# EZ_FPGA_Bridge.net
KiCad netlist of a schematic drawn in Altium Designer
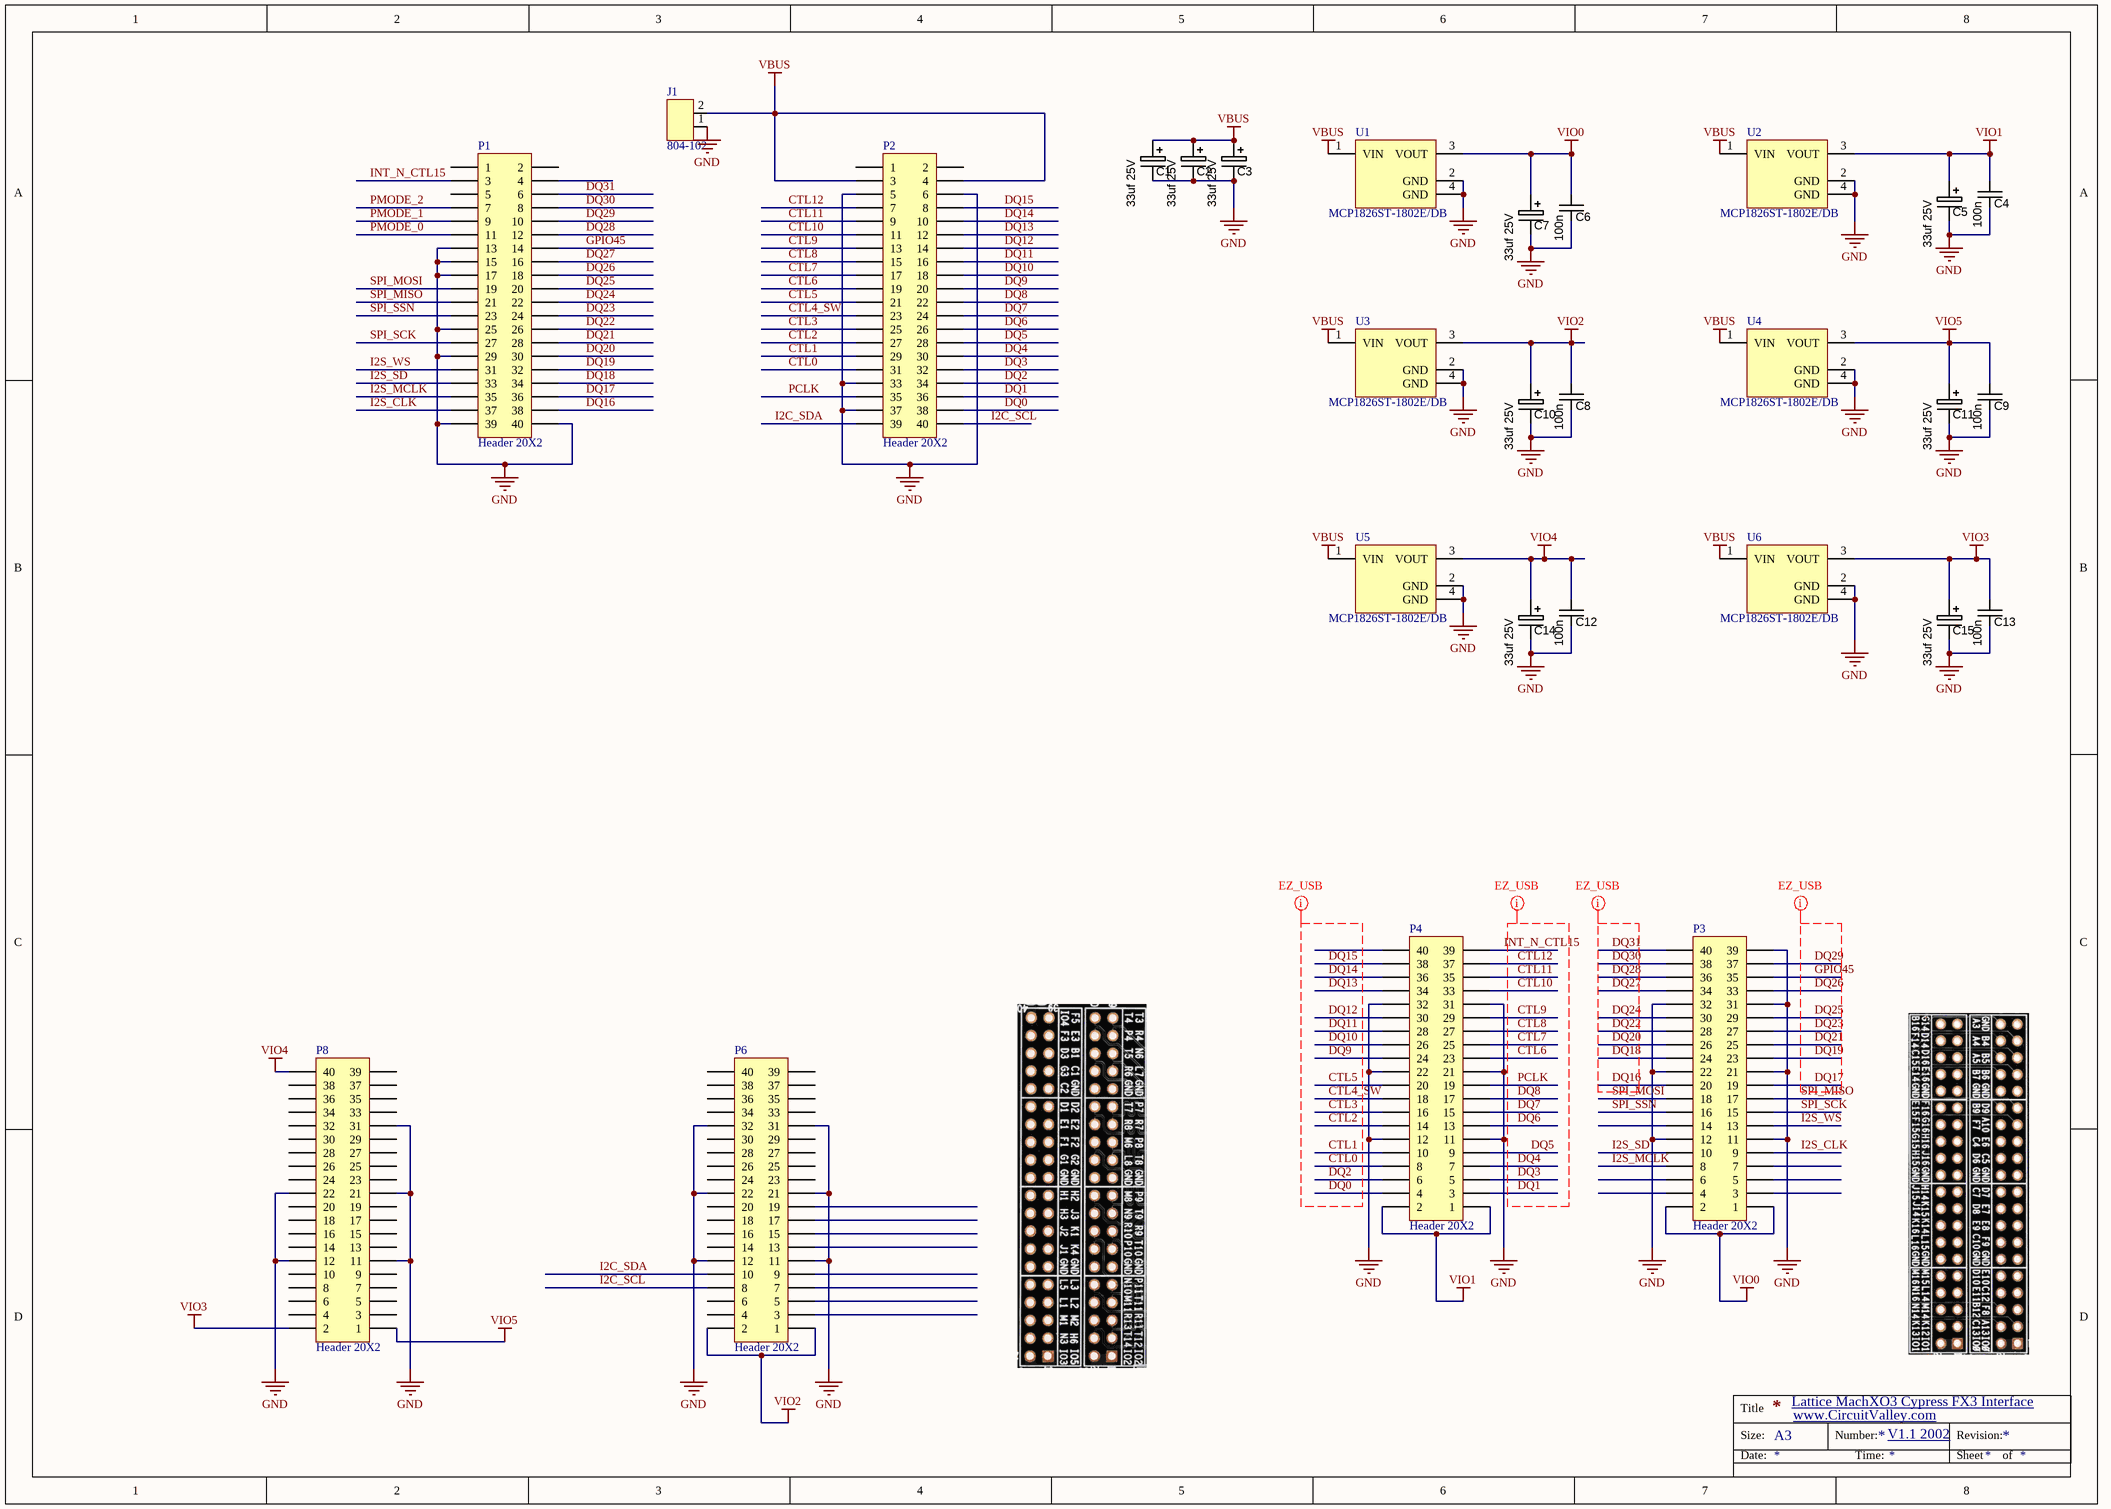
[diagram p0: EZ_FPGA_Bridge.SchDoc]

(export (version "E")
  (design (tool "Eeschema 10.0.6"))
  (components
    (comp (ref "C1")
      (value "33uf 25V")
      (footprint "CAPMP7343X310N")
      (description "Capacitor SMD Tant 330uF 20% 6V3 2917")
      (fields
        (field (name "TOLERANCE") "±20%")
        (field (name "MANUFACTURER PART NUMBER") "T520D337M006ATE015")
      )
      (libsource (lib "PBL - Capacitors") (part "CAPT_330u_2917_6V3"))
    )
    (comp (ref "C2")
      (value "33uf 25V")
      (footprint "CAPMP7343X310N")
      (description "Capacitor SMD Tant 330uF 20% 6V3 2917")
      (fields
        (field (name "TOLERANCE") "±20%")
        (field (name "MANUFACTURER PART NUMBER") "T520D337M006ATE015")
      )
      (libsource (lib "PBL - Capacitors") (part "CAPT_330u_2917_6V3"))
    )
    (comp (ref "C3")
      (value "33uf 25V")
      (footprint "CAPMP7343X310N")
      (description "Capacitor SMD Tant 330uF 20% 6V3 2917")
      (fields
        (field (name "TOLERANCE") "±20%")
        (field (name "MANUFACTURER PART NUMBER") "T520D337M006ATE015")
      )
      (libsource (lib "PBL - Capacitors") (part "CAPT_330u_2917_6V3"))
    )
    (comp (ref "C4")
      (value "100n")
      (footprint "CAPC1608N")
      (description "Capacitor SMD Cer 10pF 5% 50V NP0 0603")
      (fields (field (name "TOLERANCE") "±5%") (field (name "PART") "C0603X104K5RAC"))
      (libsource (lib "PBL - Capacitors") (part "CAPC_10p_0603_NP0_1%_50V"))
    )
    (comp (ref "C5")
      (value "33uf 25V")
      (footprint "CAPMP7343X310N")
      (description "Capacitor SMD Tant 330uF 20% 6V3 2917")
      (fields
        (field (name "TOLERANCE") "±20%")
        (field (name "MANUFACTURER PART NUMBER") "T520D337M006ATE015")
      )
      (libsource (lib "PBL - Capacitors") (part "CAPT_330u_2917_6V3"))
    )
    (comp (ref "C6")
      (value "100n")
      (footprint "CAPC1608N")
      (description "Capacitor SMD Cer 10pF 5% 50V NP0 0603")
      (fields (field (name "TOLERANCE") "±5%") (field (name "PART") "C0603X104K5RAC"))
      (libsource (lib "PBL - Capacitors") (part "CAPC_10p_0603_NP0_1%_50V"))
    )
    (comp (ref "C7")
      (value "33uf 25V")
      (footprint "CAPMP7343X310N")
      (description "Capacitor SMD Tant 330uF 20% 6V3 2917")
      (fields
        (field (name "TOLERANCE") "±20%")
        (field (name "MANUFACTURER PART NUMBER") "T520D337M006ATE015")
      )
      (libsource (lib "PBL - Capacitors") (part "CAPT_330u_2917_6V3"))
    )
    (comp (ref "C8")
      (value "100n")
      (footprint "CAPC1608N")
      (description "Capacitor SMD Cer 10pF 5% 50V NP0 0603")
      (fields (field (name "TOLERANCE") "±5%") (field (name "PART") "C0603X104K5RAC"))
      (libsource (lib "PBL - Capacitors") (part "CAPC_10p_0603_NP0_1%_50V"))
    )
    (comp (ref "C9")
      (value "100n")
      (footprint "CAPC1608N")
      (description "Capacitor SMD Cer 10pF 5% 50V NP0 0603")
      (fields (field (name "TOLERANCE") "±5%") (field (name "PART") "C0603X104K5RAC"))
      (libsource (lib "PBL - Capacitors") (part "CAPC_10p_0603_NP0_1%_50V"))
    )
    (comp (ref "C10")
      (value "33uf 25V")
      (footprint "CAPMP7343X310N")
      (description "Capacitor SMD Tant 330uF 20% 6V3 2917")
      (fields
        (field (name "TOLERANCE") "±20%")
        (field (name "MANUFACTURER PART NUMBER") "T520D337M006ATE015")
      )
      (libsource (lib "PBL - Capacitors") (part "CAPT_330u_2917_6V3"))
    )
    (comp (ref "C11")
      (value "33uf 25V")
      (footprint "CAPMP7343X310N")
      (description "Capacitor SMD Tant 330uF 20% 6V3 2917")
      (fields
        (field (name "TOLERANCE") "±20%")
        (field (name "MANUFACTURER PART NUMBER") "T520D337M006ATE015")
      )
      (libsource (lib "PBL - Capacitors") (part "CAPT_330u_2917_6V3"))
    )
    (comp (ref "C12")
      (value "100n")
      (footprint "CAPC1608N")
      (description "Capacitor SMD Cer 10pF 5% 50V NP0 0603")
      (fields (field (name "TOLERANCE") "±5%") (field (name "PART") "C0603X104K5RAC"))
      (libsource (lib "PBL - Capacitors") (part "CAPC_10p_0603_NP0_1%_50V"))
    )
    (comp (ref "C13")
      (value "100n")
      (footprint "CAPC1608N")
      (description "Capacitor SMD Cer 10pF 5% 50V NP0 0603")
      (fields (field (name "TOLERANCE") "±5%") (field (name "PART") "C0603X104K5RAC"))
      (libsource (lib "PBL - Capacitors") (part "CAPC_10p_0603_NP0_1%_50V"))
    )
    (comp (ref "C14")
      (value "33uf 25V")
      (footprint "CAPMP7343X310N")
      (description "Capacitor SMD Tant 330uF 20% 6V3 2917")
      (fields
        (field (name "TOLERANCE") "±20%")
        (field (name "MANUFACTURER PART NUMBER") "T520D337M006ATE015")
      )
      (libsource (lib "PBL - Capacitors") (part "CAPT_330u_2917_6V3"))
    )
    (comp (ref "C15")
      (value "33uf 25V")
      (footprint "CAPMP7343X310N")
      (description "Capacitor SMD Tant 330uF 20% 6V3 2917")
      (fields
        (field (name "TOLERANCE") "±20%")
        (field (name "MANUFACTURER PART NUMBER") "T520D337M006ATE015")
      )
      (libsource (lib "PBL - Capacitors") (part "CAPT_330u_2917_6V3"))
    )
    (comp (ref "J1") (value "804-102") (footprint "804-102") (libsource (lib "cvlib") (part "804-102")))
    (comp (ref "P1")
      (value "Header 20X2")
      (footprint "HDR2X20")
      (description "Header, 20-Pin, Dual row")
      (fields (field (name "PUBLISHER") "Altium Limited"))
      (libsource (lib "Miscellaneous Connectors") (part "Header 20X2"))
    )
    (comp (ref "P2")
      (value "Header 20X2")
      (footprint "HDR2X20")
      (description "Header, 20-Pin, Dual row")
      (fields (field (name "PUBLISHER") "Altium Limited"))
      (libsource (lib "Miscellaneous Connectors") (part "Header 20X2"))
    )
    (comp (ref "P3")
      (value "Header 20X2")
      (footprint "HDR2X20")
      (description "Header, 20-Pin, Dual row")
      (fields (field (name "PUBLISHER") "Altium Limited"))
      (libsource (lib "") (part "Header 20X2_1"))
    )
    (comp (ref "P4")
      (value "Header 20X2")
      (footprint "HDR2X20")
      (description "Header, 20-Pin, Dual row")
      (fields (field (name "PUBLISHER") "Altium Limited"))
      (libsource (lib "") (part "Header 20X2_1"))
    )
    (comp (ref "P6")
      (value "Header 20X2")
      (footprint "HDR2X20")
      (description "Header, 20-Pin, Dual row")
      (fields (field (name "PUBLISHER") "Altium Limited"))
      (libsource (lib "") (part "Header 20X2_1"))
    )
    (comp (ref "P8")
      (value "Header 20X2")
      (footprint "HDR2X20")
      (description "Header, 20-Pin, Dual row")
      (fields (field (name "PUBLISHER") "Altium Limited"))
      (libsource (lib "") (part "Header 20X2_1"))
    )
    (comp (ref "U1")
      (value "MCP1826ST-1802E/DB")
      (footprint "SOT-223-DB3_N")
      (fields (field (name "PUBLISHER") "Altium Limited"))
      (libsource (lib "Microchip Power Mgt Line Regulator") (part "MCP1826ST-1802E/DB"))
    )
    (comp (ref "U2")
      (value "MCP1826ST-1802E/DB")
      (footprint "SOT-223-DB3_N")
      (fields (field (name "PUBLISHER") "Altium Limited"))
      (libsource (lib "Microchip Power Mgt Line Regulator") (part "MCP1826ST-1802E/DB"))
    )
    (comp (ref "U3")
      (value "MCP1826ST-1802E/DB")
      (footprint "SOT-223-DB3_N")
      (fields (field (name "PUBLISHER") "Altium Limited"))
      (libsource (lib "Microchip Power Mgt Line Regulator") (part "MCP1826ST-1802E/DB"))
    )
    (comp (ref "U4")
      (value "MCP1826ST-1802E/DB")
      (footprint "SOT-223-DB3_N")
      (fields (field (name "PUBLISHER") "Altium Limited"))
      (libsource (lib "Microchip Power Mgt Line Regulator") (part "MCP1826ST-1802E/DB"))
    )
    (comp (ref "U5")
      (value "MCP1826ST-1802E/DB")
      (footprint "SOT-223-DB3_N")
      (fields (field (name "PUBLISHER") "Altium Limited"))
      (libsource (lib "Microchip Power Mgt Line Regulator") (part "MCP1826ST-1802E/DB"))
    )
    (comp (ref "U6")
      (value "MCP1826ST-1802E/DB")
      (footprint "SOT-223-DB3_N")
      (fields (field (name "PUBLISHER") "Altium Limited"))
      (libsource (lib "Microchip Power Mgt Line Regulator") (part "MCP1826ST-1802E/DB"))
    )
  )
  (nets
    (net (code "1") (name "/CTL0") (class "Default")
      (node (ref "P2") (pin "31") (pinfunction "31_31") (pintype "passive"))
      (node (ref "P4") (pin "8") (pinfunction "8_8") (pintype "passive"))
    )
    (net (code "2") (name "/CTL1") (class "Default")
      (node (ref "P2") (pin "29") (pinfunction "29_29") (pintype "passive"))
      (node (ref "P4") (pin "10") (pinfunction "10_10") (pintype "passive"))
    )
    (net (code "3") (name "/CTL2") (class "Default")
      (node (ref "P2") (pin "27") (pinfunction "27_27") (pintype "passive"))
      (node (ref "P4") (pin "14") (pinfunction "14_14") (pintype "passive"))
    )
    (net (code "4") (name "/CTL3") (class "Default")
      (node (ref "P2") (pin "25") (pinfunction "25_25") (pintype "passive"))
      (node (ref "P4") (pin "16") (pinfunction "16_16") (pintype "passive"))
    )
    (net (code "5") (name "/CTL4_SW") (class "Default")
      (node (ref "P2") (pin "23") (pinfunction "23_23") (pintype "passive"))
      (node (ref "P4") (pin "18") (pinfunction "18_18") (pintype "passive"))
    )
    (net (code "6") (name "/CTL5") (class "Default")
      (node (ref "P2") (pin "21") (pinfunction "21_21") (pintype "passive"))
      (node (ref "P4") (pin "20") (pinfunction "20_20") (pintype "passive"))
    )
    (net (code "7") (name "/CTL6") (class "Default")
      (node (ref "P2") (pin "19") (pinfunction "19_19") (pintype "passive"))
      (node (ref "P4") (pin "23") (pinfunction "23_23") (pintype "passive"))
    )
    (net (code "8") (name "/CTL7") (class "Default")
      (node (ref "P2") (pin "17") (pinfunction "17_17") (pintype "passive"))
      (node (ref "P4") (pin "25") (pinfunction "25_25") (pintype "passive"))
    )
    (net (code "9") (name "/CTL8") (class "Default")
      (node (ref "P2") (pin "15") (pinfunction "15_15") (pintype "passive"))
      (node (ref "P4") (pin "27") (pinfunction "27_27") (pintype "passive"))
    )
    (net (code "10") (name "/CTL9") (class "Default")
      (node (ref "P2") (pin "13") (pinfunction "13_13") (pintype "passive"))
      (node (ref "P4") (pin "29") (pinfunction "29_29") (pintype "passive"))
    )
    (net (code "11") (name "/CTL10") (class "Default")
      (node (ref "P2") (pin "11") (pinfunction "11_11") (pintype "passive"))
      (node (ref "P4") (pin "33") (pinfunction "33_33") (pintype "passive"))
    )
    (net (code "12") (name "/CTL11") (class "Default")
      (node (ref "P2") (pin "9") (pinfunction "9_9") (pintype "passive"))
      (node (ref "P4") (pin "35") (pinfunction "35_35") (pintype "passive"))
    )
    (net (code "13") (name "/CTL12") (class "Default")
      (node (ref "P2") (pin "7") (pinfunction "7_7") (pintype "passive"))
      (node (ref "P4") (pin "37") (pinfunction "37_37") (pintype "passive"))
    )
    (net (code "14") (name "/DQ0") (class "Default")
      (node (ref "P2") (pin "38") (pinfunction "38_38") (pintype "passive"))
      (node (ref "P4") (pin "4") (pinfunction "4_4") (pintype "passive"))
    )
    (net (code "15") (name "/DQ1") (class "Default")
      (node (ref "P2") (pin "36") (pinfunction "36_36") (pintype "passive"))
      (node (ref "P4") (pin "3") (pinfunction "3_3") (pintype "passive"))
    )
    (net (code "16") (name "/DQ2") (class "Default")
      (node (ref "P2") (pin "34") (pinfunction "34_34") (pintype "passive"))
      (node (ref "P4") (pin "6") (pinfunction "6_6") (pintype "passive"))
    )
    (net (code "17") (name "/DQ3") (class "Default")
      (node (ref "P2") (pin "32") (pinfunction "32_32") (pintype "passive"))
      (node (ref "P4") (pin "5") (pinfunction "5_5") (pintype "passive"))
    )
    (net (code "18") (name "/DQ4") (class "Default")
      (node (ref "P2") (pin "30") (pinfunction "30_30") (pintype "passive"))
      (node (ref "P4") (pin "7") (pinfunction "7_7") (pintype "passive"))
    )
    (net (code "19") (name "/DQ5") (class "Default")
      (node (ref "P2") (pin "28") (pinfunction "28_28") (pintype "passive"))
      (node (ref "P4") (pin "9") (pinfunction "9_9") (pintype "passive"))
    )
    (net (code "20") (name "/DQ6") (class "Default")
      (node (ref "P2") (pin "26") (pinfunction "26_26") (pintype "passive"))
      (node (ref "P4") (pin "13") (pinfunction "13_13") (pintype "passive"))
    )
    (net (code "21") (name "/DQ7") (class "Default")
      (node (ref "P2") (pin "24") (pinfunction "24_24") (pintype "passive"))
      (node (ref "P4") (pin "15") (pinfunction "15_15") (pintype "passive"))
    )
    (net (code "22") (name "/DQ8") (class "Default")
      (node (ref "P2") (pin "22") (pinfunction "22_22") (pintype "passive"))
      (node (ref "P4") (pin "17") (pinfunction "17_17") (pintype "passive"))
    )
    (net (code "23") (name "/DQ9") (class "Default")
      (node (ref "P2") (pin "20") (pinfunction "20_20") (pintype "passive"))
      (node (ref "P4") (pin "24") (pinfunction "24_24") (pintype "passive"))
    )
    (net (code "24") (name "/DQ10") (class "Default")
      (node (ref "P2") (pin "18") (pinfunction "18_18") (pintype "passive"))
      (node (ref "P4") (pin "26") (pinfunction "26_26") (pintype "passive"))
    )
    (net (code "25") (name "/DQ11") (class "Default")
      (node (ref "P2") (pin "16") (pinfunction "16_16") (pintype "passive"))
      (node (ref "P4") (pin "28") (pinfunction "28_28") (pintype "passive"))
    )
    (net (code "26") (name "/DQ12") (class "Default")
      (node (ref "P2") (pin "14") (pinfunction "14_14") (pintype "passive"))
      (node (ref "P4") (pin "30") (pinfunction "30_30") (pintype "passive"))
    )
    (net (code "27") (name "/DQ13") (class "Default")
      (node (ref "P2") (pin "12") (pinfunction "12_12") (pintype "passive"))
      (node (ref "P4") (pin "34") (pinfunction "34_34") (pintype "passive"))
    )
    (net (code "28") (name "/DQ14") (class "Default")
      (node (ref "P2") (pin "10") (pinfunction "10_10") (pintype "passive"))
      (node (ref "P4") (pin "36") (pinfunction "36_36") (pintype "passive"))
    )
    (net (code "29") (name "/DQ15") (class "Default")
      (node (ref "P2") (pin "8") (pinfunction "8_8") (pintype "passive"))
      (node (ref "P4") (pin "38") (pinfunction "38_38") (pintype "passive"))
    )
    (net (code "30") (name "/DQ16") (class "Default")
      (node (ref "P1") (pin "38") (pinfunction "38_38") (pintype "passive"))
      (node (ref "P3") (pin "20") (pinfunction "20_20") (pintype "passive"))
    )
    (net (code "31") (name "/DQ17") (class "Default")
      (node (ref "P1") (pin "36") (pinfunction "36_36") (pintype "passive"))
      (node (ref "P3") (pin "19") (pinfunction "19_19") (pintype "passive"))
    )
    (net (code "32") (name "/DQ18") (class "Default")
      (node (ref "P1") (pin "34") (pinfunction "34_34") (pintype "passive"))
      (node (ref "P3") (pin "24") (pinfunction "24_24") (pintype "passive"))
    )
    (net (code "33") (name "/DQ19") (class "Default")
      (node (ref "P1") (pin "32") (pinfunction "32_32") (pintype "passive"))
      (node (ref "P3") (pin "23") (pinfunction "23_23") (pintype "passive"))
    )
    (net (code "34") (name "/DQ20") (class "Default")
      (node (ref "P1") (pin "30") (pinfunction "30_30") (pintype "passive"))
      (node (ref "P3") (pin "26") (pinfunction "26_26") (pintype "passive"))
    )
    (net (code "35") (name "/DQ21") (class "Default")
      (node (ref "P1") (pin "28") (pinfunction "28_28") (pintype "passive"))
      (node (ref "P3") (pin "25") (pinfunction "25_25") (pintype "passive"))
    )
    (net (code "36") (name "/DQ22") (class "Default")
      (node (ref "P1") (pin "26") (pinfunction "26_26") (pintype "passive"))
      (node (ref "P3") (pin "28") (pinfunction "28_28") (pintype "passive"))
    )
    (net (code "37") (name "/DQ23") (class "Default")
      (node (ref "P1") (pin "24") (pinfunction "24_24") (pintype "passive"))
      (node (ref "P3") (pin "27") (pinfunction "27_27") (pintype "passive"))
    )
    (net (code "38") (name "/DQ24") (class "Default")
      (node (ref "P1") (pin "22") (pinfunction "22_22") (pintype "passive"))
      (node (ref "P3") (pin "30") (pinfunction "30_30") (pintype "passive"))
    )
    (net (code "39") (name "/DQ25") (class "Default")
      (node (ref "P1") (pin "20") (pinfunction "20_20") (pintype "passive"))
      (node (ref "P3") (pin "29") (pinfunction "29_29") (pintype "passive"))
    )
    (net (code "40") (name "/DQ26") (class "Default")
      (node (ref "P1") (pin "18") (pinfunction "18_18") (pintype "passive"))
      (node (ref "P3") (pin "33") (pinfunction "33_33") (pintype "passive"))
    )
    (net (code "41") (name "/DQ27") (class "Default")
      (node (ref "P1") (pin "16") (pinfunction "16_16") (pintype "passive"))
      (node (ref "P3") (pin "34") (pinfunction "34_34") (pintype "passive"))
    )
    (net (code "42") (name "/DQ28") (class "Default")
      (node (ref "P1") (pin "12") (pinfunction "12_12") (pintype "passive"))
      (node (ref "P3") (pin "36") (pinfunction "36_36") (pintype "passive"))
    )
    (net (code "43") (name "/DQ29") (class "Default")
      (node (ref "P1") (pin "10") (pinfunction "10_10") (pintype "passive"))
      (node (ref "P3") (pin "37") (pinfunction "37_37") (pintype "passive"))
    )
    (net (code "44") (name "/DQ30") (class "Default")
      (node (ref "P1") (pin "8") (pinfunction "8_8") (pintype "passive"))
      (node (ref "P3") (pin "38") (pinfunction "38_38") (pintype "passive"))
    )
    (net (code "45") (name "/DQ31") (class "Default")
      (node (ref "P1") (pin "6") (pinfunction "6_6") (pintype "passive"))
      (node (ref "P3") (pin "40") (pinfunction "40_40") (pintype "passive"))
    )
    (net (code "46") (name "/GPIO45") (class "Default")
      (node (ref "P1") (pin "14") (pinfunction "14_14") (pintype "passive"))
      (node (ref "P3") (pin "35") (pinfunction "35_35") (pintype "passive"))
    )
    (net (code "47") (name "/I2C_SCL") (class "Default")
      (node (ref "P2") (pin "40") (pinfunction "40_40") (pintype "passive"))
      (node (ref "P6") (pin "8") (pinfunction "8_8") (pintype "passive"))
    )
    (net (code "48") (name "/I2C_SDA") (class "Default")
      (node (ref "P2") (pin "39") (pinfunction "39_39") (pintype "passive"))
      (node (ref "P6") (pin "10") (pinfunction "10_10") (pintype "passive"))
    )
    (net (code "49") (name "/I2S_CLK") (class "Default")
      (node (ref "P1") (pin "37") (pinfunction "37_37") (pintype "passive"))
      (node (ref "P3") (pin "9") (pinfunction "9_9") (pintype "passive"))
    )
    (net (code "50") (name "/I2S_MCLK") (class "Default")
      (node (ref "P1") (pin "35") (pinfunction "35_35") (pintype "passive"))
      (node (ref "P3") (pin "8") (pinfunction "8_8") (pintype "passive"))
    )
    (net (code "51") (name "/I2S_SD") (class "Default")
      (node (ref "P1") (pin "33") (pinfunction "33_33") (pintype "passive"))
      (node (ref "P3") (pin "10") (pinfunction "10_10") (pintype "passive"))
    )
    (net (code "52") (name "/I2S_WS") (class "Default")
      (node (ref "P1") (pin "31") (pinfunction "31_31") (pintype "passive"))
      (node (ref "P3") (pin "13") (pinfunction "13_13") (pintype "passive"))
    )
    (net (code "53") (name "/INT_N_CTL15") (class "Default")
      (node (ref "P1") (pin "3") (pinfunction "3_3") (pintype "passive"))
      (node (ref "P4") (pin "39") (pinfunction "39_39") (pintype "passive"))
    )
    (net (code "54") (name "/PCLK") (class "Default")
      (node (ref "P2") (pin "35") (pinfunction "35_35") (pintype "passive"))
      (node (ref "P4") (pin "19") (pinfunction "19_19") (pintype "passive"))
    )
    (net (code "55") (name "/PMODE_0") (class "Default")
      (node (ref "P1") (pin "11") (pinfunction "11_11") (pintype "passive"))
    )
    (net (code "56") (name "/PMODE_1") (class "Default")
      (node (ref "P1") (pin "9") (pinfunction "9_9") (pintype "passive"))
    )
    (net (code "57") (name "/PMODE_2") (class "Default")
      (node (ref "P1") (pin "7") (pinfunction "7_7") (pintype "passive"))
    )
    (net (code "58") (name "/SPI_MISO") (class "Default")
      (node (ref "P1") (pin "21") (pinfunction "21_21") (pintype "passive"))
      (node (ref "P3") (pin "17") (pinfunction "17_17") (pintype "passive"))
    )
    (net (code "59") (name "/SPI_MOSI") (class "Default")
      (node (ref "P1") (pin "19") (pinfunction "19_19") (pintype "passive"))
      (node (ref "P3") (pin "18") (pinfunction "18_18") (pintype "passive"))
    )
    (net (code "60") (name "/SPI_SCK") (class "Default")
      (node (ref "P1") (pin "27") (pinfunction "27_27") (pintype "passive"))
      (node (ref "P3") (pin "15") (pinfunction "15_15") (pintype "passive"))
    )
    (net (code "61") (name "/SPI_SSN") (class "Default")
      (node (ref "P1") (pin "23") (pinfunction "23_23") (pintype "passive"))
      (node (ref "P3") (pin "16") (pinfunction "16_16") (pintype "passive"))
    )
    (net (code "62") (name "GND") (class "Default")
      (node (ref "C1") (pin "2") (pintype "passive"))
      (node (ref "C10") (pin "2") (pintype "passive"))
      (node (ref "C11") (pin "2") (pintype "passive"))
      (node (ref "C12") (pin "1") (pintype "passive"))
      (node (ref "C13") (pin "1") (pintype "passive"))
      (node (ref "C14") (pin "2") (pintype "passive"))
      (node (ref "C15") (pin "2") (pintype "passive"))
      (node (ref "C2") (pin "2") (pintype "passive"))
      (node (ref "C3") (pin "2") (pintype "passive"))
      (node (ref "C4") (pin "1") (pintype "passive"))
      (node (ref "C5") (pin "2") (pintype "passive"))
      (node (ref "C6") (pin "1") (pintype "passive"))
      (node (ref "C7") (pin "2") (pintype "passive"))
      (node (ref "C8") (pin "1") (pintype "passive"))
      (node (ref "C9") (pin "1") (pintype "passive"))
      (node (ref "J1") (pin "1") (pinfunction "PW_1") (pintype "passive"))
      (node (ref "P1") (pin "13") (pinfunction "13_13") (pintype "passive"))
      (node (ref "P1") (pin "15") (pinfunction "15_15") (pintype "passive"))
      (node (ref "P1") (pin "17") (pinfunction "17_17") (pintype "passive"))
      (node (ref "P1") (pin "25") (pinfunction "25_25") (pintype "passive"))
      (node (ref "P1") (pin "29") (pinfunction "29_29") (pintype "passive"))
      (node (ref "P1") (pin "39") (pinfunction "39_39") (pintype "passive"))
      (node (ref "P1") (pin "40") (pinfunction "40_40") (pintype "passive"))
      (node (ref "P2") (pin "33") (pinfunction "33_33") (pintype "passive"))
      (node (ref "P2") (pin "37") (pinfunction "37_37") (pintype "passive"))
      (node (ref "P2") (pin "5") (pinfunction "5_5") (pintype "passive"))
      (node (ref "P2") (pin "6") (pinfunction "6_6") (pintype "passive"))
      (node (ref "P3") (pin "11") (pinfunction "11_11") (pintype "passive"))
      (node (ref "P3") (pin "12") (pinfunction "12_12") (pintype "passive"))
      (node (ref "P3") (pin "21") (pinfunction "21_21") (pintype "passive"))
      (node (ref "P3") (pin "22") (pinfunction "22_22") (pintype "passive"))
      (node (ref "P3") (pin "31") (pinfunction "31_31") (pintype "passive"))
      (node (ref "P3") (pin "32") (pinfunction "32_32") (pintype "passive"))
      (node (ref "P3") (pin "39") (pinfunction "39_39") (pintype "passive"))
      (node (ref "P4") (pin "11") (pinfunction "11_11") (pintype "passive"))
      (node (ref "P4") (pin "12") (pinfunction "12_12") (pintype "passive"))
      (node (ref "P4") (pin "21") (pinfunction "21_21") (pintype "passive"))
      (node (ref "P4") (pin "22") (pinfunction "22_22") (pintype "passive"))
      (node (ref "P4") (pin "31") (pinfunction "31_31") (pintype "passive"))
      (node (ref "P4") (pin "32") (pinfunction "32_32") (pintype "passive"))
      (node (ref "P6") (pin "11") (pinfunction "11_11") (pintype "passive"))
      (node (ref "P6") (pin "12") (pinfunction "12_12") (pintype "passive"))
      (node (ref "P6") (pin "21") (pinfunction "21_21") (pintype "passive"))
      (node (ref "P6") (pin "22") (pinfunction "22_22") (pintype "passive"))
      (node (ref "P6") (pin "31") (pinfunction "31_31") (pintype "passive"))
      (node (ref "P6") (pin "32") (pinfunction "32_32") (pintype "passive"))
      (node (ref "P8") (pin "11") (pinfunction "11_11") (pintype "passive"))
      (node (ref "P8") (pin "12") (pinfunction "12_12") (pintype "passive"))
      (node (ref "P8") (pin "21") (pinfunction "21_21") (pintype "passive"))
      (node (ref "P8") (pin "22") (pinfunction "22_22") (pintype "passive"))
      (node (ref "P8") (pin "31") (pinfunction "31_31") (pintype "passive"))
      (node (ref "U1") (pin "2") (pinfunction "GND_2") (pintype "power_in"))
      (node (ref "U1") (pin "4") (pinfunction "GND_4") (pintype "power_in"))
      (node (ref "U2") (pin "2") (pinfunction "GND_2") (pintype "power_in"))
      (node (ref "U2") (pin "4") (pinfunction "GND_4") (pintype "power_in"))
      (node (ref "U3") (pin "2") (pinfunction "GND_2") (pintype "power_in"))
      (node (ref "U3") (pin "4") (pinfunction "GND_4") (pintype "power_in"))
      (node (ref "U4") (pin "2") (pinfunction "GND_2") (pintype "power_in"))
      (node (ref "U4") (pin "4") (pinfunction "GND_4") (pintype "power_in"))
      (node (ref "U5") (pin "2") (pinfunction "GND_2") (pintype "power_in"))
      (node (ref "U5") (pin "4") (pinfunction "GND_4") (pintype "power_in"))
      (node (ref "U6") (pin "2") (pinfunction "GND_2") (pintype "power_in"))
      (node (ref "U6") (pin "4") (pinfunction "GND_4") (pintype "power_in"))
    )
    (net (code "63") (name "VBUS") (class "Default")
      (node (ref "C1") (pin "1") (pintype "passive"))
      (node (ref "C2") (pin "1") (pintype "passive"))
      (node (ref "C3") (pin "1") (pintype "passive"))
      (node (ref "J1") (pin "2") (pinfunction "PW_2") (pintype "passive"))
      (node (ref "P2") (pin "3") (pinfunction "3_3") (pintype "passive"))
      (node (ref "P2") (pin "4") (pinfunction "4_4") (pintype "passive"))
      (node (ref "U1") (pin "1") (pinfunction "VIN_1") (pintype "power_in"))
      (node (ref "U2") (pin "1") (pinfunction "VIN_1") (pintype "power_in"))
      (node (ref "U3") (pin "1") (pinfunction "VIN_1") (pintype "power_in"))
      (node (ref "U4") (pin "1") (pinfunction "VIN_1") (pintype "power_in"))
      (node (ref "U5") (pin "1") (pinfunction "VIN_1") (pintype "power_in"))
      (node (ref "U6") (pin "1") (pinfunction "VIN_1") (pintype "power_in"))
    )
    (net (code "64") (name "VIO0") (class "Default")
      (node (ref "C6") (pin "2") (pintype "passive"))
      (node (ref "C7") (pin "1") (pintype "passive"))
      (node (ref "P3") (pin "1") (pinfunction "1_1") (pintype "passive"))
      (node (ref "P3") (pin "2") (pinfunction "2_2") (pintype "passive"))
      (node (ref "U1") (pin "3") (pinfunction "VOUT_3") (pintype "power_in"))
    )
    (net (code "65") (name "VIO1") (class "Default")
      (node (ref "C4") (pin "2") (pintype "passive"))
      (node (ref "C5") (pin "1") (pintype "passive"))
      (node (ref "P4") (pin "1") (pinfunction "1_1") (pintype "passive"))
      (node (ref "P4") (pin "2") (pinfunction "2_2") (pintype "passive"))
      (node (ref "U2") (pin "3") (pinfunction "VOUT_3") (pintype "power_in"))
    )
    (net (code "66") (name "VIO2") (class "Default")
      (node (ref "C10") (pin "1") (pintype "passive"))
      (node (ref "C8") (pin "2") (pintype "passive"))
      (node (ref "P6") (pin "1") (pinfunction "1_1") (pintype "passive"))
      (node (ref "P6") (pin "2") (pinfunction "2_2") (pintype "passive"))
      (node (ref "U3") (pin "3") (pinfunction "VOUT_3") (pintype "power_in"))
    )
    (net (code "67") (name "VIO3") (class "Default")
      (node (ref "C13") (pin "2") (pintype "passive"))
      (node (ref "C15") (pin "1") (pintype "passive"))
      (node (ref "P8") (pin "2") (pinfunction "2_2") (pintype "passive"))
      (node (ref "U6") (pin "3") (pinfunction "VOUT_3") (pintype "power_in"))
    )
    (net (code "68") (name "VIO4") (class "Default")
      (node (ref "C12") (pin "2") (pintype "passive"))
      (node (ref "C14") (pin "1") (pintype "passive"))
      (node (ref "P8") (pin "40") (pinfunction "40_40") (pintype "passive"))
      (node (ref "U5") (pin "3") (pinfunction "VOUT_3") (pintype "power_in"))
    )
    (net (code "69") (name "VIO5") (class "Default")
      (node (ref "C11") (pin "1") (pintype "passive"))
      (node (ref "C9") (pin "2") (pintype "passive"))
      (node (ref "P8") (pin "1") (pinfunction "1_1") (pintype "passive"))
      (node (ref "U4") (pin "3") (pinfunction "VOUT_3") (pintype "power_in"))
    )
    (net (code "70") (name "unconnected-(P1-Pad1)") (class "Default")
      (node (ref "P1") (pin "1") (pinfunction "1_1") (pintype "passive"))
    )
    (net (code "71") (name "unconnected-(P1-Pad2)") (class "Default")
      (node (ref "P1") (pin "2") (pinfunction "2_2") (pintype "passive"))
    )
    (net (code "72") (name "unconnected-(P1-Pad4)") (class "Default")
      (node (ref "P1") (pin "4") (pinfunction "4_4") (pintype "passive"))
    )
    (net (code "73") (name "unconnected-(P1-Pad5)") (class "Default")
      (node (ref "P1") (pin "5") (pinfunction "5_5") (pintype "passive"))
    )
    (net (code "74") (name "unconnected-(P2-Pad1)") (class "Default")
      (node (ref "P2") (pin "1") (pinfunction "1_1") (pintype "passive"))
    )
    (net (code "75") (name "unconnected-(P2-Pad2)") (class "Default")
      (node (ref "P2") (pin "2") (pinfunction "2_2") (pintype "passive"))
    )
    (net (code "76") (name "unconnected-(P3-Pad3)") (class "Default")
      (node (ref "P3") (pin "3") (pinfunction "3_3") (pintype "passive"))
    )
    (net (code "77") (name "unconnected-(P3-Pad4)") (class "Default")
      (node (ref "P3") (pin "4") (pinfunction "4_4") (pintype "passive"))
    )
    (net (code "78") (name "unconnected-(P3-Pad5)") (class "Default")
      (node (ref "P3") (pin "5") (pinfunction "5_5") (pintype "passive"))
    )
    (net (code "79") (name "unconnected-(P3-Pad6)") (class "Default")
      (node (ref "P3") (pin "6") (pinfunction "6_6") (pintype "passive"))
    )
    (net (code "80") (name "unconnected-(P3-Pad7)") (class "Default")
      (node (ref "P3") (pin "7") (pinfunction "7_7") (pintype "passive"))
    )
    (net (code "81") (name "unconnected-(P3-Pad14)") (class "Default")
      (node (ref "P3") (pin "14") (pinfunction "14_14") (pintype "passive"))
    )
    (net (code "82") (name "unconnected-(P4-Pad40)") (class "Default")
      (node (ref "P4") (pin "40") (pinfunction "40_40") (pintype "passive"))
    )
    (net (code "83") (name "unconnected-(P6-Pad3)") (class "Default")
      (node (ref "P6") (pin "3") (pinfunction "3_3") (pintype "passive"))
    )
    (net (code "84") (name "unconnected-(P6-Pad4)") (class "Default")
      (node (ref "P6") (pin "4") (pinfunction "4_4") (pintype "passive"))
    )
    (net (code "85") (name "unconnected-(P6-Pad5)") (class "Default")
      (node (ref "P6") (pin "5") (pinfunction "5_5") (pintype "passive"))
    )
    (net (code "86") (name "unconnected-(P6-Pad6)") (class "Default")
      (node (ref "P6") (pin "6") (pinfunction "6_6") (pintype "passive"))
    )
    (net (code "87") (name "unconnected-(P6-Pad7)") (class "Default")
      (node (ref "P6") (pin "7") (pinfunction "7_7") (pintype "passive"))
    )
    (net (code "88") (name "unconnected-(P6-Pad9)") (class "Default")
      (node (ref "P6") (pin "9") (pinfunction "9_9") (pintype "passive"))
    )
    (net (code "89") (name "unconnected-(P6-Pad13)") (class "Default")
      (node (ref "P6") (pin "13") (pinfunction "13_13") (pintype "passive"))
    )
    (net (code "90") (name "unconnected-(P6-Pad14)") (class "Default")
      (node (ref "P6") (pin "14") (pinfunction "14_14") (pintype "passive"))
    )
    (net (code "91") (name "unconnected-(P6-Pad15)") (class "Default")
      (node (ref "P6") (pin "15") (pinfunction "15_15") (pintype "passive"))
    )
    (net (code "92") (name "unconnected-(P6-Pad16)") (class "Default")
      (node (ref "P6") (pin "16") (pinfunction "16_16") (pintype "passive"))
    )
    (net (code "93") (name "unconnected-(P6-Pad17)") (class "Default")
      (node (ref "P6") (pin "17") (pinfunction "17_17") (pintype "passive"))
    )
    (net (code "94") (name "unconnected-(P6-Pad18)") (class "Default")
      (node (ref "P6") (pin "18") (pinfunction "18_18") (pintype "passive"))
    )
    (net (code "95") (name "unconnected-(P6-Pad19)") (class "Default")
      (node (ref "P6") (pin "19") (pinfunction "19_19") (pintype "passive"))
    )
    (net (code "96") (name "unconnected-(P6-Pad20)") (class "Default")
      (node (ref "P6") (pin "20") (pinfunction "20_20") (pintype "passive"))
    )
    (net (code "97") (name "unconnected-(P6-Pad23)") (class "Default")
      (node (ref "P6") (pin "23") (pinfunction "23_23") (pintype "passive"))
    )
    (net (code "98") (name "unconnected-(P6-Pad24)") (class "Default")
      (node (ref "P6") (pin "24") (pinfunction "24_24") (pintype "passive"))
    )
    (net (code "99") (name "unconnected-(P6-Pad25)") (class "Default")
      (node (ref "P6") (pin "25") (pinfunction "25_25") (pintype "passive"))
    )
    (net (code "100") (name "unconnected-(P6-Pad26)") (class "Default")
      (node (ref "P6") (pin "26") (pinfunction "26_26") (pintype "passive"))
    )
    (net (code "101") (name "unconnected-(P6-Pad27)") (class "Default")
      (node (ref "P6") (pin "27") (pinfunction "27_27") (pintype "passive"))
    )
    (net (code "102") (name "unconnected-(P6-Pad28)") (class "Default")
      (node (ref "P6") (pin "28") (pinfunction "28_28") (pintype "passive"))
    )
    (net (code "103") (name "unconnected-(P6-Pad29)") (class "Default")
      (node (ref "P6") (pin "29") (pinfunction "29_29") (pintype "passive"))
    )
    (net (code "104") (name "unconnected-(P6-Pad30)") (class "Default")
      (node (ref "P6") (pin "30") (pinfunction "30_30") (pintype "passive"))
    )
    (net (code "105") (name "unconnected-(P6-Pad33)") (class "Default")
      (node (ref "P6") (pin "33") (pinfunction "33_33") (pintype "passive"))
    )
    (net (code "106") (name "unconnected-(P6-Pad34)") (class "Default")
      (node (ref "P6") (pin "34") (pinfunction "34_34") (pintype "passive"))
    )
    (net (code "107") (name "unconnected-(P6-Pad35)") (class "Default")
      (node (ref "P6") (pin "35") (pinfunction "35_35") (pintype "passive"))
    )
    (net (code "108") (name "unconnected-(P6-Pad36)") (class "Default")
      (node (ref "P6") (pin "36") (pinfunction "36_36") (pintype "passive"))
    )
    (net (code "109") (name "unconnected-(P6-Pad37)") (class "Default")
      (node (ref "P6") (pin "37") (pinfunction "37_37") (pintype "passive"))
    )
    (net (code "110") (name "unconnected-(P6-Pad38)") (class "Default")
      (node (ref "P6") (pin "38") (pinfunction "38_38") (pintype "passive"))
    )
    (net (code "111") (name "unconnected-(P6-Pad39)") (class "Default")
      (node (ref "P6") (pin "39") (pinfunction "39_39") (pintype "passive"))
    )
    (net (code "112") (name "unconnected-(P6-Pad40)") (class "Default")
      (node (ref "P6") (pin "40") (pinfunction "40_40") (pintype "passive"))
    )
    (net (code "113") (name "unconnected-(P8-Pad3)") (class "Default")
      (node (ref "P8") (pin "3") (pinfunction "3_3") (pintype "passive"))
    )
    (net (code "114") (name "unconnected-(P8-Pad4)") (class "Default")
      (node (ref "P8") (pin "4") (pinfunction "4_4") (pintype "passive"))
    )
    (net (code "115") (name "unconnected-(P8-Pad5)") (class "Default")
      (node (ref "P8") (pin "5") (pinfunction "5_5") (pintype "passive"))
    )
    (net (code "116") (name "unconnected-(P8-Pad6)") (class "Default")
      (node (ref "P8") (pin "6") (pinfunction "6_6") (pintype "passive"))
    )
    (net (code "117") (name "unconnected-(P8-Pad7)") (class "Default")
      (node (ref "P8") (pin "7") (pinfunction "7_7") (pintype "passive"))
    )
    (net (code "118") (name "unconnected-(P8-Pad8)") (class "Default")
      (node (ref "P8") (pin "8") (pinfunction "8_8") (pintype "passive"))
    )
    (net (code "119") (name "unconnected-(P8-Pad9)") (class "Default")
      (node (ref "P8") (pin "9") (pinfunction "9_9") (pintype "passive"))
    )
    (net (code "120") (name "unconnected-(P8-Pad10)") (class "Default")
      (node (ref "P8") (pin "10") (pinfunction "10_10") (pintype "passive"))
    )
    (net (code "121") (name "unconnected-(P8-Pad13)") (class "Default")
      (node (ref "P8") (pin "13") (pinfunction "13_13") (pintype "passive"))
    )
    (net (code "122") (name "unconnected-(P8-Pad14)") (class "Default")
      (node (ref "P8") (pin "14") (pinfunction "14_14") (pintype "passive"))
    )
    (net (code "123") (name "unconnected-(P8-Pad15)") (class "Default")
      (node (ref "P8") (pin "15") (pinfunction "15_15") (pintype "passive"))
    )
    (net (code "124") (name "unconnected-(P8-Pad16)") (class "Default")
      (node (ref "P8") (pin "16") (pinfunction "16_16") (pintype "passive"))
    )
    (net (code "125") (name "unconnected-(P8-Pad17)") (class "Default")
      (node (ref "P8") (pin "17") (pinfunction "17_17") (pintype "passive"))
    )
    (net (code "126") (name "unconnected-(P8-Pad18)") (class "Default")
      (node (ref "P8") (pin "18") (pinfunction "18_18") (pintype "passive"))
    )
    (net (code "127") (name "unconnected-(P8-Pad19)") (class "Default")
      (node (ref "P8") (pin "19") (pinfunction "19_19") (pintype "passive"))
    )
    (net (code "128") (name "unconnected-(P8-Pad20)") (class "Default")
      (node (ref "P8") (pin "20") (pinfunction "20_20") (pintype "passive"))
    )
    (net (code "129") (name "unconnected-(P8-Pad23)") (class "Default")
      (node (ref "P8") (pin "23") (pinfunction "23_23") (pintype "passive"))
    )
    (net (code "130") (name "unconnected-(P8-Pad24)") (class "Default")
      (node (ref "P8") (pin "24") (pinfunction "24_24") (pintype "passive"))
    )
    (net (code "131") (name "unconnected-(P8-Pad25)") (class "Default")
      (node (ref "P8") (pin "25") (pinfunction "25_25") (pintype "passive"))
    )
    (net (code "132") (name "unconnected-(P8-Pad26)") (class "Default")
      (node (ref "P8") (pin "26") (pinfunction "26_26") (pintype "passive"))
    )
    (net (code "133") (name "unconnected-(P8-Pad27)") (class "Default")
      (node (ref "P8") (pin "27") (pinfunction "27_27") (pintype "passive"))
    )
    (net (code "134") (name "unconnected-(P8-Pad28)") (class "Default")
      (node (ref "P8") (pin "28") (pinfunction "28_28") (pintype "passive"))
    )
    (net (code "135") (name "unconnected-(P8-Pad29)") (class "Default")
      (node (ref "P8") (pin "29") (pinfunction "29_29") (pintype "passive"))
    )
    (net (code "136") (name "unconnected-(P8-Pad30)") (class "Default")
      (node (ref "P8") (pin "30") (pinfunction "30_30") (pintype "passive"))
    )
    (net (code "137") (name "unconnected-(P8-Pad32)") (class "Default")
      (node (ref "P8") (pin "32") (pinfunction "32_32") (pintype "passive"))
    )
    (net (code "138") (name "unconnected-(P8-Pad33)") (class "Default")
      (node (ref "P8") (pin "33") (pinfunction "33_33") (pintype "passive"))
    )
    (net (code "139") (name "unconnected-(P8-Pad34)") (class "Default")
      (node (ref "P8") (pin "34") (pinfunction "34_34") (pintype "passive"))
    )
    (net (code "140") (name "unconnected-(P8-Pad35)") (class "Default")
      (node (ref "P8") (pin "35") (pinfunction "35_35") (pintype "passive"))
    )
    (net (code "141") (name "unconnected-(P8-Pad36)") (class "Default")
      (node (ref "P8") (pin "36") (pinfunction "36_36") (pintype "passive"))
    )
    (net (code "142") (name "unconnected-(P8-Pad37)") (class "Default")
      (node (ref "P8") (pin "37") (pinfunction "37_37") (pintype "passive"))
    )
    (net (code "143") (name "unconnected-(P8-Pad38)") (class "Default")
      (node (ref "P8") (pin "38") (pinfunction "38_38") (pintype "passive"))
    )
    (net (code "144") (name "unconnected-(P8-Pad39)") (class "Default")
      (node (ref "P8") (pin "39") (pinfunction "39_39") (pintype "passive"))
    )
  )
)
